# Nav_Retro_IO.net
KiCad netlist of a schematic drawn in Altium Designer
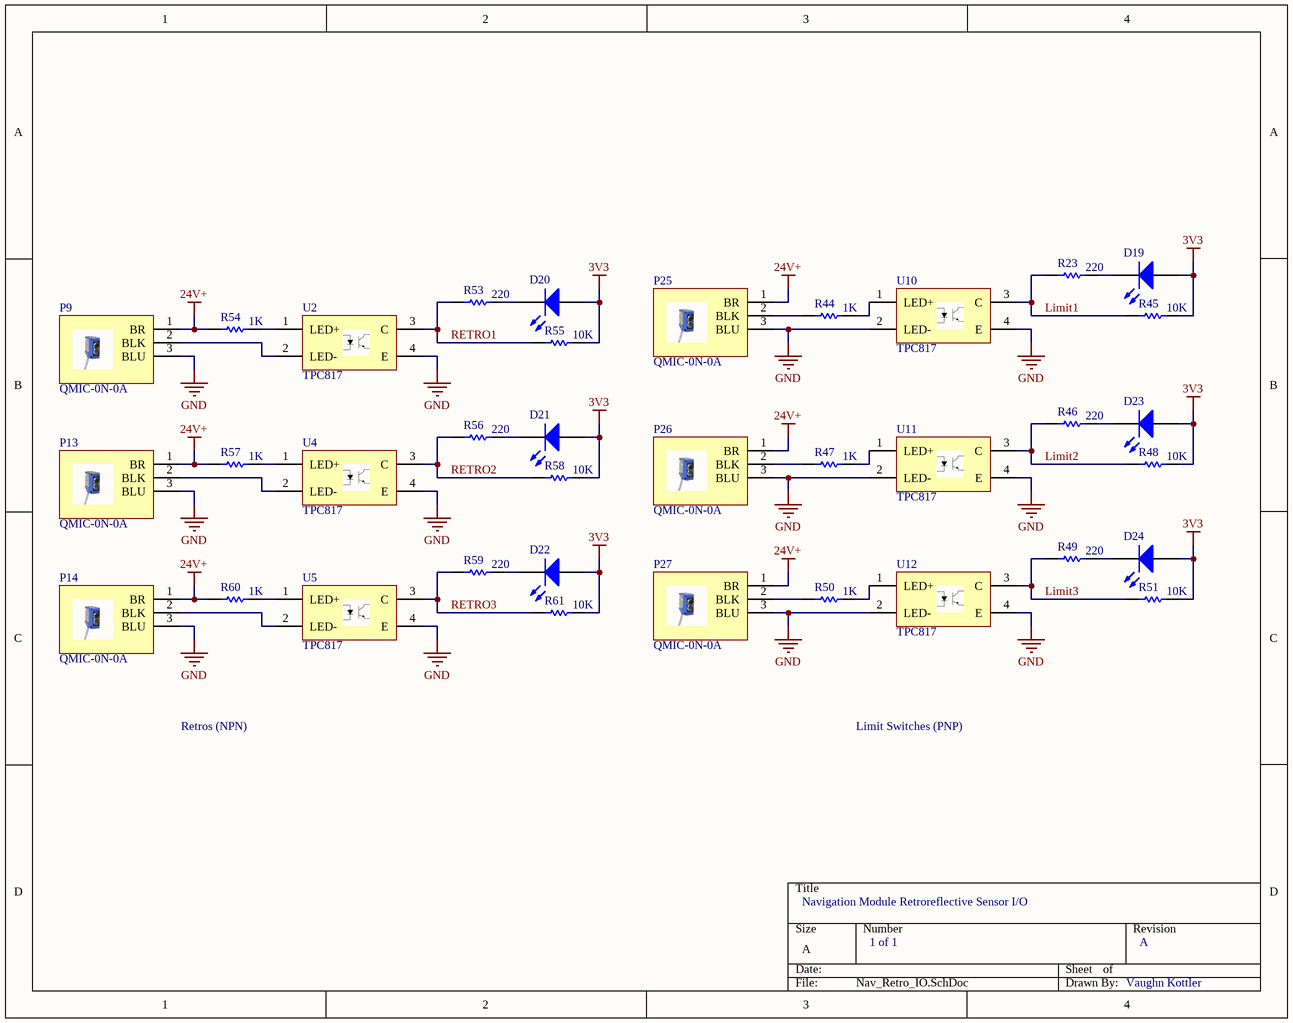
[diagram p0: Nav_Retro_IO.SchDoc]

(export (version "E")
  (design (tool "Eeschema 10.0.6"))
  (components
    (comp (ref "D19")
      (value "LED2")
      (footprint "3.2X1.6X1.1")
      (description "Typical RED, GREEN, YELLOW, AMBER GaAs LED")
      (fields (field (name "PUBLISHER") "Altium Limited"))
      (libsource (lib "Miscellaneous Devices") (part "LED2"))
    )
    (comp (ref "D20")
      (value "LED2")
      (footprint "3.2X1.6X1.1")
      (description "Typical RED, GREEN, YELLOW, AMBER GaAs LED")
      (fields (field (name "PUBLISHER") "Altium Limited"))
      (libsource (lib "Miscellaneous Devices") (part "LED2"))
    )
    (comp (ref "D21")
      (value "LED2")
      (footprint "3.2X1.6X1.1")
      (description "Typical RED, GREEN, YELLOW, AMBER GaAs LED")
      (fields (field (name "PUBLISHER") "Altium Limited"))
      (libsource (lib "Miscellaneous Devices") (part "LED2"))
    )
    (comp (ref "D22")
      (value "LED2")
      (footprint "3.2X1.6X1.1")
      (description "Typical RED, GREEN, YELLOW, AMBER GaAs LED")
      (fields (field (name "PUBLISHER") "Altium Limited"))
      (libsource (lib "Miscellaneous Devices") (part "LED2"))
    )
    (comp (ref "D23")
      (value "LED2")
      (footprint "3.2X1.6X1.1")
      (description "Typical RED, GREEN, YELLOW, AMBER GaAs LED")
      (fields (field (name "PUBLISHER") "Altium Limited"))
      (libsource (lib "Miscellaneous Devices") (part "LED2"))
    )
    (comp (ref "D24")
      (value "LED2")
      (footprint "3.2X1.6X1.1")
      (description "Typical RED, GREEN, YELLOW, AMBER GaAs LED")
      (fields (field (name "PUBLISHER") "Altium Limited"))
      (libsource (lib "Miscellaneous Devices") (part "LED2"))
    )
    (comp (ref "P9")
      (value "QMIC-0N-0A")
      (footprint "3POS TERM BLOCK")
      (description "Retroreflective Sensor")
      (libsource (lib "connector") (part "QMIC-0N-0A"))
    )
    (comp (ref "P13")
      (value "QMIC-0N-0A")
      (footprint "3POS TERM BLOCK")
      (description "Retroreflective Sensor")
      (libsource (lib "connector") (part "QMIC-0N-0A"))
    )
    (comp (ref "P14")
      (value "QMIC-0N-0A")
      (footprint "3POS TERM BLOCK")
      (description "Retroreflective Sensor")
      (libsource (lib "connector") (part "QMIC-0N-0A"))
    )
    (comp (ref "P25")
      (value "QMIC-0N-0A")
      (footprint "3POS TERM BLOCK")
      (description "Retroreflective Sensor")
      (libsource (lib "connector") (part "QMIC-0N-0A"))
    )
    (comp (ref "P26")
      (value "QMIC-0N-0A")
      (footprint "3POS TERM BLOCK")
      (description "Retroreflective Sensor")
      (libsource (lib "connector") (part "QMIC-0N-0A"))
    )
    (comp (ref "P27")
      (value "QMIC-0N-0A")
      (footprint "3POS TERM BLOCK")
      (description "Retroreflective Sensor")
      (libsource (lib "connector") (part "QMIC-0N-0A"))
    )
    (comp (ref "R23")
      (value "220")
      (footprint "6-0805_M")
      (description "Resistor")
      (fields (field (name "Comment") "Res1") (field (name "PUBLISHER") "Altium Limited"))
      (libsource (lib "Miscellaneous Devices") (part "Res1"))
    )
    (comp (ref "R44")
      (value "1K")
      (footprint "6-0805_M")
      (description "Resistor")
      (fields (field (name "Comment") "Res1") (field (name "PUBLISHER") "Altium Limited"))
      (libsource (lib "Miscellaneous Devices") (part "Res1"))
    )
    (comp (ref "R45")
      (value "10K")
      (footprint "6-0805_M")
      (description "Resistor")
      (fields (field (name "Comment") "Res1") (field (name "PUBLISHER") "Altium Limited"))
      (libsource (lib "Miscellaneous Devices") (part "Res1"))
    )
    (comp (ref "R46")
      (value "220")
      (footprint "6-0805_M")
      (description "Resistor")
      (fields (field (name "Comment") "Res1") (field (name "PUBLISHER") "Altium Limited"))
      (libsource (lib "Miscellaneous Devices") (part "Res1"))
    )
    (comp (ref "R47")
      (value "1K")
      (footprint "6-0805_M")
      (description "Resistor")
      (fields (field (name "Comment") "Res1") (field (name "PUBLISHER") "Altium Limited"))
      (libsource (lib "Miscellaneous Devices") (part "Res1"))
    )
    (comp (ref "R48")
      (value "10K")
      (footprint "6-0805_M")
      (description "Resistor")
      (fields (field (name "Comment") "Res1") (field (name "PUBLISHER") "Altium Limited"))
      (libsource (lib "Miscellaneous Devices") (part "Res1"))
    )
    (comp (ref "R49")
      (value "220")
      (footprint "6-0805_M")
      (description "Resistor")
      (fields (field (name "Comment") "Res1") (field (name "PUBLISHER") "Altium Limited"))
      (libsource (lib "Miscellaneous Devices") (part "Res1"))
    )
    (comp (ref "R50")
      (value "1K")
      (footprint "6-0805_M")
      (description "Resistor")
      (fields (field (name "Comment") "Res1") (field (name "PUBLISHER") "Altium Limited"))
      (libsource (lib "Miscellaneous Devices") (part "Res1"))
    )
    (comp (ref "R51")
      (value "10K")
      (footprint "6-0805_M")
      (description "Resistor")
      (fields (field (name "Comment") "Res1") (field (name "PUBLISHER") "Altium Limited"))
      (libsource (lib "Miscellaneous Devices") (part "Res1"))
    )
    (comp (ref "R53")
      (value "220")
      (footprint "6-0805_M")
      (description "Resistor")
      (fields (field (name "Comment") "Res1") (field (name "PUBLISHER") "Altium Limited"))
      (libsource (lib "Miscellaneous Devices") (part "Res1"))
    )
    (comp (ref "R54")
      (value "1K")
      (footprint "6-0805_M")
      (description "Resistor")
      (fields (field (name "Comment") "Res1") (field (name "PUBLISHER") "Altium Limited"))
      (libsource (lib "Miscellaneous Devices") (part "Res1"))
    )
    (comp (ref "R55")
      (value "10K")
      (footprint "6-0805_M")
      (description "Resistor")
      (fields (field (name "Comment") "Res1") (field (name "PUBLISHER") "Altium Limited"))
      (libsource (lib "Miscellaneous Devices") (part "Res1"))
    )
    (comp (ref "R56")
      (value "220")
      (footprint "6-0805_M")
      (description "Resistor")
      (fields (field (name "Comment") "Res1") (field (name "PUBLISHER") "Altium Limited"))
      (libsource (lib "Miscellaneous Devices") (part "Res1"))
    )
    (comp (ref "R57")
      (value "1K")
      (footprint "6-0805_M")
      (description "Resistor")
      (fields (field (name "Comment") "Res1") (field (name "PUBLISHER") "Altium Limited"))
      (libsource (lib "Miscellaneous Devices") (part "Res1"))
    )
    (comp (ref "R58")
      (value "10K")
      (footprint "6-0805_M")
      (description "Resistor")
      (fields (field (name "Comment") "Res1") (field (name "PUBLISHER") "Altium Limited"))
      (libsource (lib "Miscellaneous Devices") (part "Res1"))
    )
    (comp (ref "R59")
      (value "220")
      (footprint "6-0805_M")
      (description "Resistor")
      (fields (field (name "Comment") "Res1") (field (name "PUBLISHER") "Altium Limited"))
      (libsource (lib "Miscellaneous Devices") (part "Res1"))
    )
    (comp (ref "R60")
      (value "1K")
      (footprint "6-0805_M")
      (description "Resistor")
      (fields (field (name "Comment") "Res1") (field (name "PUBLISHER") "Altium Limited"))
      (libsource (lib "Miscellaneous Devices") (part "Res1"))
    )
    (comp (ref "R61")
      (value "10K")
      (footprint "6-0805_M")
      (description "Resistor")
      (fields (field (name "Comment") "Res1") (field (name "PUBLISHER") "Altium Limited"))
      (libsource (lib "Miscellaneous Devices") (part "Res1"))
    )
    (comp (ref "U2")
      (value "TPC817")
      (footprint "4-SOP")
      (description "Opto-Coupler")
      (libsource (lib "ic") (part "TPC817"))
    )
    (comp (ref "U4")
      (value "TPC817")
      (footprint "4-SOP")
      (description "Opto-Coupler")
      (libsource (lib "ic") (part "TPC817"))
    )
    (comp (ref "U5")
      (value "TPC817")
      (footprint "4-SOP")
      (description "Opto-Coupler")
      (libsource (lib "ic") (part "TPC817"))
    )
    (comp (ref "U10")
      (value "TPC817")
      (footprint "4-SOP")
      (description "Opto-Coupler")
      (libsource (lib "ic") (part "TPC817"))
    )
    (comp (ref "U11")
      (value "TPC817")
      (footprint "4-SOP")
      (description "Opto-Coupler")
      (libsource (lib "ic") (part "TPC817"))
    )
    (comp (ref "U12")
      (value "TPC817")
      (footprint "4-SOP")
      (description "Opto-Coupler")
      (libsource (lib "ic") (part "TPC817"))
    )
  )
  (nets
    (net (code "1") (name "/Limit1") (class "Default")
      (node (ref "R23") (pin "1") (pinfunction "1_1") (pintype "passive"))
      (node (ref "R45") (pin "1") (pinfunction "1_1") (pintype "passive"))
      (node (ref "U10") (pin "3") (pinfunction "C_3") (pintype "open_collector"))
    )
    (net (code "2") (name "/Limit2") (class "Default")
      (node (ref "R46") (pin "1") (pinfunction "1_1") (pintype "passive"))
      (node (ref "R48") (pin "1") (pinfunction "1_1") (pintype "passive"))
      (node (ref "U11") (pin "3") (pinfunction "C_3") (pintype "open_collector"))
    )
    (net (code "3") (name "/Limit3") (class "Default")
      (node (ref "R49") (pin "1") (pinfunction "1_1") (pintype "passive"))
      (node (ref "R51") (pin "1") (pinfunction "1_1") (pintype "passive"))
      (node (ref "U12") (pin "3") (pinfunction "C_3") (pintype "open_collector"))
    )
    (net (code "4") (name "/RETRO1") (class "Default")
      (node (ref "R53") (pin "1") (pinfunction "1_1") (pintype "passive"))
      (node (ref "R55") (pin "1") (pinfunction "1_1") (pintype "passive"))
      (node (ref "U2") (pin "3") (pinfunction "C_3") (pintype "open_collector"))
    )
    (net (code "5") (name "/RETRO2") (class "Default")
      (node (ref "R56") (pin "1") (pinfunction "1_1") (pintype "passive"))
      (node (ref "R58") (pin "1") (pinfunction "1_1") (pintype "passive"))
      (node (ref "U4") (pin "3") (pinfunction "C_3") (pintype "open_collector"))
    )
    (net (code "6") (name "/RETRO3") (class "Default")
      (node (ref "R59") (pin "1") (pinfunction "1_1") (pintype "passive"))
      (node (ref "R61") (pin "1") (pinfunction "1_1") (pintype "passive"))
      (node (ref "U5") (pin "3") (pinfunction "C_3") (pintype "open_collector"))
    )
    (net (code "7") (name "3V3") (class "Default")
      (node (ref "D19") (pin "1") (pinfunction "A_1") (pintype "passive"))
      (node (ref "D20") (pin "1") (pinfunction "A_1") (pintype "passive"))
      (node (ref "D21") (pin "1") (pinfunction "A_1") (pintype "passive"))
      (node (ref "D22") (pin "1") (pinfunction "A_1") (pintype "passive"))
      (node (ref "D23") (pin "1") (pinfunction "A_1") (pintype "passive"))
      (node (ref "D24") (pin "1") (pinfunction "A_1") (pintype "passive"))
      (node (ref "R45") (pin "2") (pinfunction "2_2") (pintype "passive"))
      (node (ref "R48") (pin "2") (pinfunction "2_2") (pintype "passive"))
      (node (ref "R51") (pin "2") (pinfunction "2_2") (pintype "passive"))
      (node (ref "R55") (pin "2") (pinfunction "2_2") (pintype "passive"))
      (node (ref "R58") (pin "2") (pinfunction "2_2") (pintype "passive"))
      (node (ref "R61") (pin "2") (pinfunction "2_2") (pintype "passive"))
    )
    (net (code "8") (name "24V+") (class "Default")
      (node (ref "P13") (pin "1") (pinfunction "BR_1") (pintype "power_in"))
      (node (ref "P14") (pin "1") (pinfunction "BR_1") (pintype "power_in"))
      (node (ref "P25") (pin "1") (pinfunction "BR_1") (pintype "power_in"))
      (node (ref "P26") (pin "1") (pinfunction "BR_1") (pintype "power_in"))
      (node (ref "P27") (pin "1") (pinfunction "BR_1") (pintype "power_in"))
      (node (ref "P9") (pin "1") (pinfunction "BR_1") (pintype "power_in"))
      (node (ref "R54") (pin "1") (pinfunction "1_1") (pintype "passive"))
      (node (ref "R57") (pin "1") (pinfunction "1_1") (pintype "passive"))
      (node (ref "R60") (pin "1") (pinfunction "1_1") (pintype "passive"))
    )
    (net (code "9") (name "GND") (class "Default")
      (node (ref "P13") (pin "3") (pinfunction "BLU_3") (pintype "power_in"))
      (node (ref "P14") (pin "3") (pinfunction "BLU_3") (pintype "power_in"))
      (node (ref "P25") (pin "3") (pinfunction "BLU_3") (pintype "power_in"))
      (node (ref "P26") (pin "3") (pinfunction "BLU_3") (pintype "power_in"))
      (node (ref "P27") (pin "3") (pinfunction "BLU_3") (pintype "power_in"))
      (node (ref "P9") (pin "3") (pinfunction "BLU_3") (pintype "power_in"))
      (node (ref "U10") (pin "2") (pinfunction "LED-_2") (pintype "passive"))
      (node (ref "U10") (pin "4") (pinfunction "E_4") (pintype "open_emitter"))
      (node (ref "U11") (pin "2") (pinfunction "LED-_2") (pintype "passive"))
      (node (ref "U11") (pin "4") (pinfunction "E_4") (pintype "open_emitter"))
      (node (ref "U12") (pin "2") (pinfunction "LED-_2") (pintype "passive"))
      (node (ref "U12") (pin "4") (pinfunction "E_4") (pintype "open_emitter"))
      (node (ref "U2") (pin "4") (pinfunction "E_4") (pintype "open_emitter"))
      (node (ref "U4") (pin "4") (pinfunction "E_4") (pintype "open_emitter"))
      (node (ref "U5") (pin "4") (pinfunction "E_4") (pintype "open_emitter"))
    )
    (net (code "10") (name "Net-(D19-K)") (class "Default")
      (node (ref "D19") (pin "2") (pinfunction "K_2") (pintype "passive"))
      (node (ref "R23") (pin "2") (pinfunction "2_2") (pintype "passive"))
    )
    (net (code "11") (name "Net-(D20-K)") (class "Default")
      (node (ref "D20") (pin "2") (pinfunction "K_2") (pintype "passive"))
      (node (ref "R53") (pin "2") (pinfunction "2_2") (pintype "passive"))
    )
    (net (code "12") (name "Net-(D21-K)") (class "Default")
      (node (ref "D21") (pin "2") (pinfunction "K_2") (pintype "passive"))
      (node (ref "R56") (pin "2") (pinfunction "2_2") (pintype "passive"))
    )
    (net (code "13") (name "Net-(D22-K)") (class "Default")
      (node (ref "D22") (pin "2") (pinfunction "K_2") (pintype "passive"))
      (node (ref "R59") (pin "2") (pinfunction "2_2") (pintype "passive"))
    )
    (net (code "14") (name "Net-(D23-K)") (class "Default")
      (node (ref "D23") (pin "2") (pinfunction "K_2") (pintype "passive"))
      (node (ref "R46") (pin "2") (pinfunction "2_2") (pintype "passive"))
    )
    (net (code "15") (name "Net-(D24-K)") (class "Default")
      (node (ref "D24") (pin "2") (pinfunction "K_2") (pintype "passive"))
      (node (ref "R49") (pin "2") (pinfunction "2_2") (pintype "passive"))
    )
    (net (code "16") (name "Net-(P9-BLK)") (class "Default")
      (node (ref "P9") (pin "2") (pinfunction "BLK_2") (pintype "open_collector"))
      (node (ref "U2") (pin "2") (pinfunction "LED-_2") (pintype "passive"))
    )
    (net (code "17") (name "Net-(P13-BLK)") (class "Default")
      (node (ref "P13") (pin "2") (pinfunction "BLK_2") (pintype "open_collector"))
      (node (ref "U4") (pin "2") (pinfunction "LED-_2") (pintype "passive"))
    )
    (net (code "18") (name "Net-(P14-BLK)") (class "Default")
      (node (ref "P14") (pin "2") (pinfunction "BLK_2") (pintype "open_collector"))
      (node (ref "U5") (pin "2") (pinfunction "LED-_2") (pintype "passive"))
    )
    (net (code "19") (name "Net-(P25-BLK)") (class "Default")
      (node (ref "P25") (pin "2") (pinfunction "BLK_2") (pintype "open_collector"))
      (node (ref "R44") (pin "1") (pinfunction "1_1") (pintype "passive"))
    )
    (net (code "20") (name "Net-(P26-BLK)") (class "Default")
      (node (ref "P26") (pin "2") (pinfunction "BLK_2") (pintype "open_collector"))
      (node (ref "R47") (pin "1") (pinfunction "1_1") (pintype "passive"))
    )
    (net (code "21") (name "Net-(P27-BLK)") (class "Default")
      (node (ref "P27") (pin "2") (pinfunction "BLK_2") (pintype "open_collector"))
      (node (ref "R50") (pin "1") (pinfunction "1_1") (pintype "passive"))
    )
    (net (code "22") (name "Net-(U2-LED+)") (class "Default")
      (node (ref "R54") (pin "2") (pinfunction "2_2") (pintype "passive"))
      (node (ref "U2") (pin "1") (pinfunction "LED+_1") (pintype "passive"))
    )
    (net (code "23") (name "Net-(U4-LED+)") (class "Default")
      (node (ref "R57") (pin "2") (pinfunction "2_2") (pintype "passive"))
      (node (ref "U4") (pin "1") (pinfunction "LED+_1") (pintype "passive"))
    )
    (net (code "24") (name "Net-(U5-LED+)") (class "Default")
      (node (ref "R60") (pin "2") (pinfunction "2_2") (pintype "passive"))
      (node (ref "U5") (pin "1") (pinfunction "LED+_1") (pintype "passive"))
    )
    (net (code "25") (name "Net-(U10-LED+)") (class "Default")
      (node (ref "R44") (pin "2") (pinfunction "2_2") (pintype "passive"))
      (node (ref "U10") (pin "1") (pinfunction "LED+_1") (pintype "passive"))
    )
    (net (code "26") (name "Net-(U11-LED+)") (class "Default")
      (node (ref "R47") (pin "2") (pinfunction "2_2") (pintype "passive"))
      (node (ref "U11") (pin "1") (pinfunction "LED+_1") (pintype "passive"))
    )
    (net (code "27") (name "Net-(U12-LED+)") (class "Default")
      (node (ref "R50") (pin "2") (pinfunction "2_2") (pintype "passive"))
      (node (ref "U12") (pin "1") (pinfunction "LED+_1") (pintype "passive"))
    )
  )
)
